# 21-M2_GNSS.net
KiCad netlist of a schematic drawn in Altium Designer
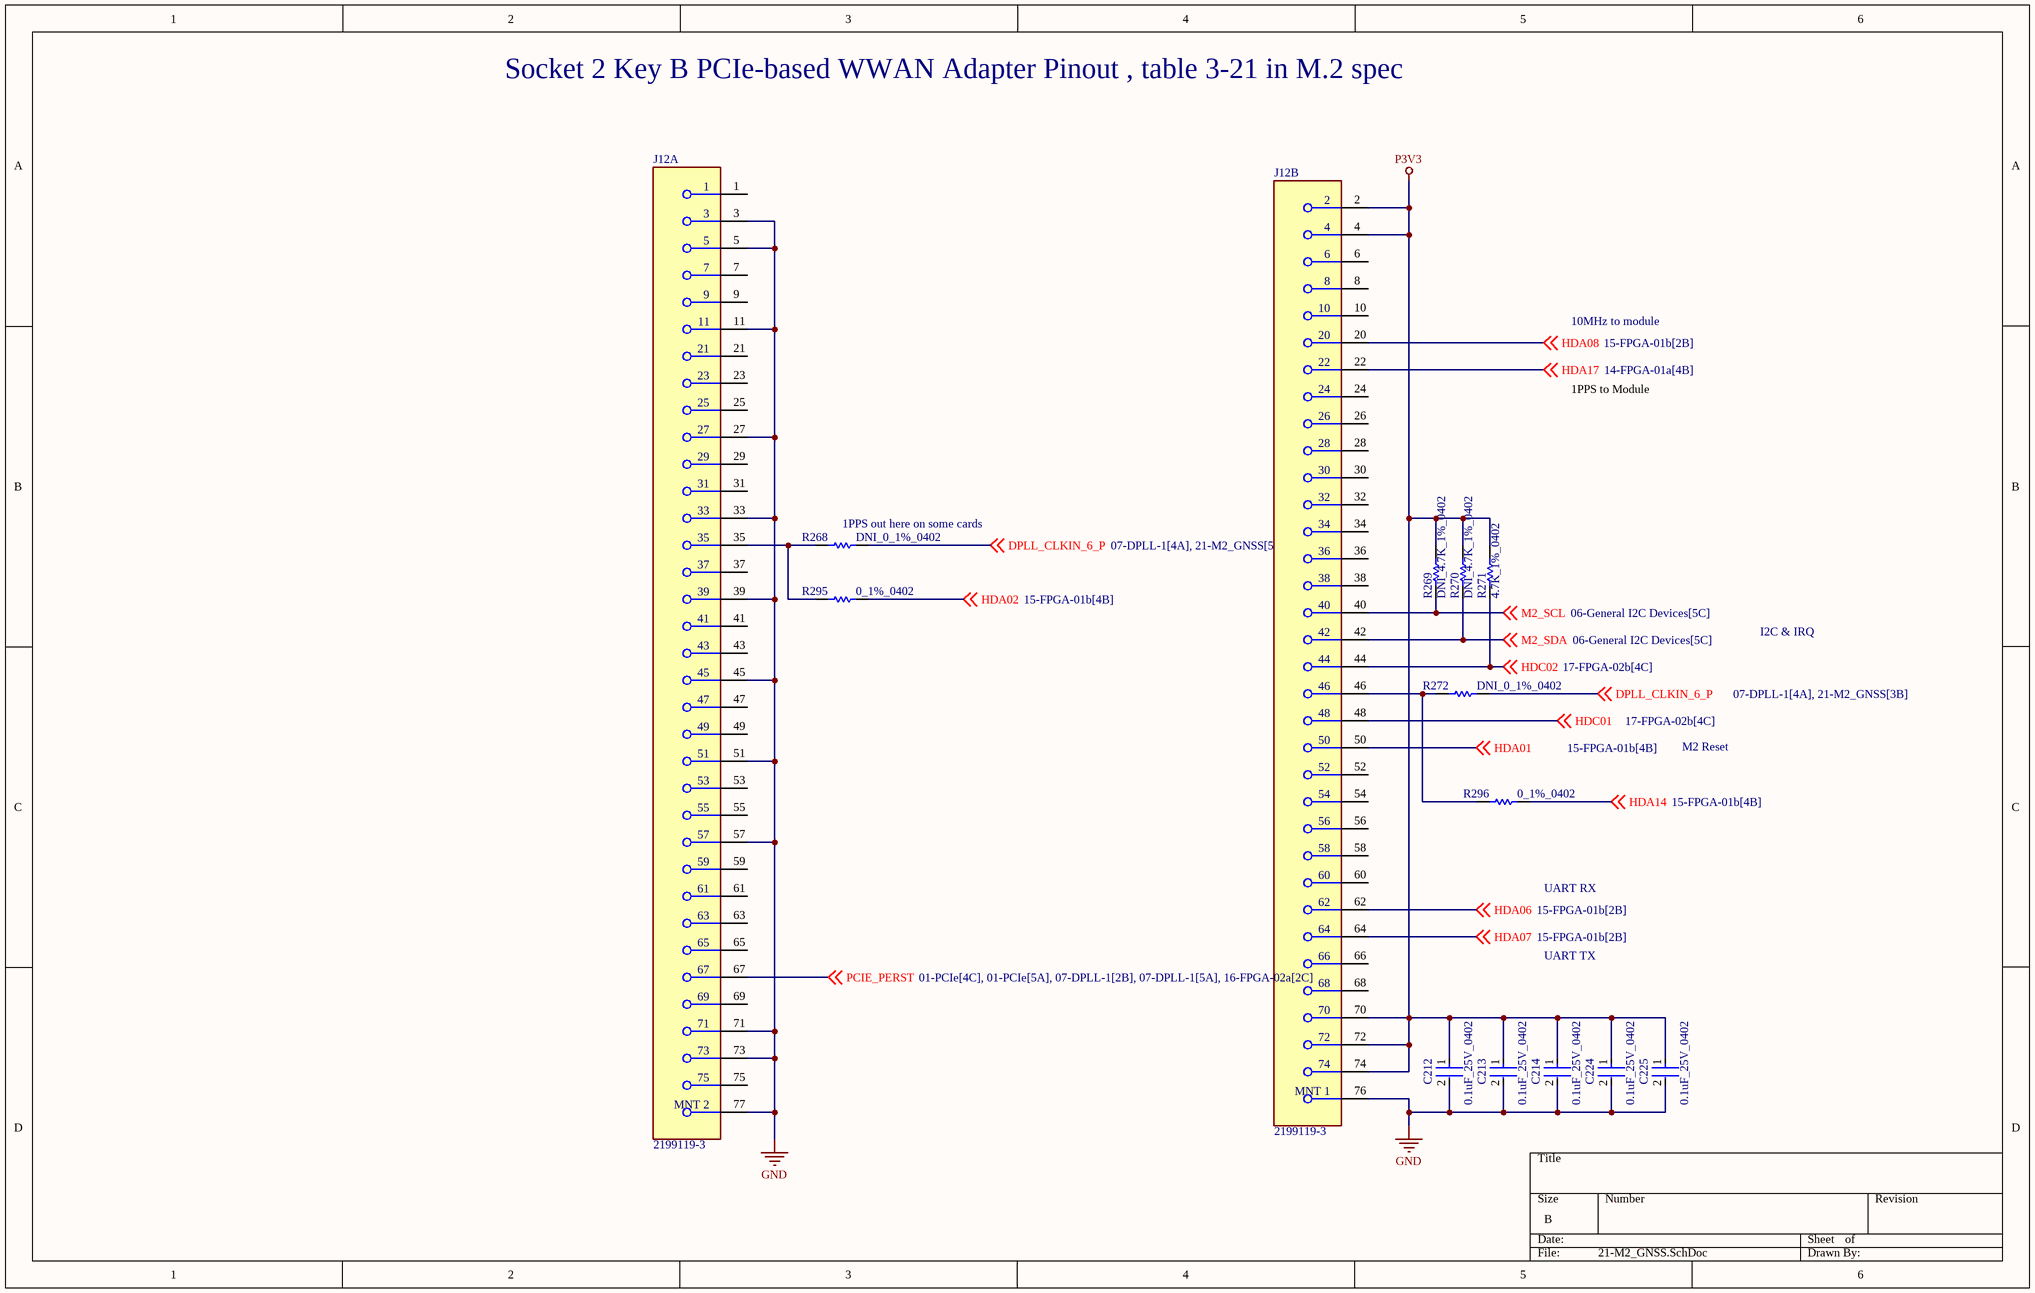
[diagram p0: 21-M2_GNSS.SchDoc]

(export (version "E")
  (design (tool "Eeschema 10.0.6"))
  (components
    (comp (ref "C212")
      (value "0.1uF_25V_0402")
      (footprint "FP-0402-L_1_0_1-W_0_5_0_1-IPC_C")
      (description "General Purpose Ceramic Capacitor, 0402, 100nF, 10%, X7R, 15%, 25V")
      (fields (field (name "VOLTAGE") "25V") (field (name "TOLERANCE") "10%"))
      (libsource (lib "Altium Content Vault") (part "b4654b650e69147ec39a6b967a45e02"))
    )
    (comp (ref "C213")
      (value "0.1uF_25V_0402")
      (footprint "FP-0402-L_1_0_1-W_0_5_0_1-IPC_C")
      (description "General Purpose Ceramic Capacitor, 0402, 100nF, 10%, X7R, 15%, 25V")
      (fields (field (name "VOLTAGE") "25V") (field (name "TOLERANCE") "10%"))
      (libsource (lib "Altium Content Vault") (part "b4654b650e69147ec39a6b967a45e02"))
    )
    (comp (ref "C214")
      (value "0.1uF_25V_0402")
      (footprint "FP-0402-L_1_0_1-W_0_5_0_1-IPC_C")
      (description "General Purpose Ceramic Capacitor, 0402, 100nF, 10%, X7R, 15%, 25V")
      (fields (field (name "VOLTAGE") "25V") (field (name "TOLERANCE") "10%"))
      (libsource (lib "Altium Content Vault") (part "b4654b650e69147ec39a6b967a45e02"))
    )
    (comp (ref "C224")
      (value "0.1uF_25V_0402")
      (footprint "FP-0402-L_1_0_1-W_0_5_0_1-IPC_C")
      (description "General Purpose Ceramic Capacitor, 0402, 100nF, 10%, X7R, 15%, 25V")
      (fields (field (name "VOLTAGE") "25V") (field (name "TOLERANCE") "10%"))
      (libsource (lib "Altium Content Vault") (part "b4654b650e69147ec39a6b967a45e02"))
    )
    (comp (ref "C225")
      (value "0.1uF_25V_0402")
      (footprint "FP-0402-L_1_0_1-W_0_5_0_1-IPC_C")
      (description "General Purpose Ceramic Capacitor, 0402, 100nF, 10%, X7R, 15%, 25V")
      (fields (field (name "VOLTAGE") "25V") (field (name "TOLERANCE") "10%"))
      (libsource (lib "Altium Content Vault") (part "b4654b650e69147ec39a6b967a45e02"))
    )
    (comp (ref "J12")
      (value "2199119-3")
      (footprint "FP-2199119-3-MFG")
      (description "CONN M.2 FEMALE 67POS 0.020 GOLD")
      (libsource (lib "Altium Content Vault") (part "a14843ccfa78e5d0b739856168502fb"))
    )
    (comp (ref "R268")
      (value "DNI_0_1%_0402")
      (footprint "RESC1005X40X25LL05T05")
      (description "Chip Resistor, 0 Ohm, 0.1 W, -55 to 155 degC, 0402 (1005 Metric), RoHS, Tape and Reel")
      (fields (field (name "MANUFACTURER") "Panasonic") (field (name "TOLERANCE") "5%"))
      (libsource (lib "Altium Content Vault") (part "RES-2"))
    )
    (comp (ref "R269")
      (value "DNI_4.7K_1%_0402")
      (footprint "RESC1005X40X25NL10T10")
      (fields (field (name "MANUFACTURER") "Bourns") (field (name "PART NUMBER") "CR0402-FX-4701GLF"))
      (libsource (lib "Altium Content Vault") (part "RES"))
    )
    (comp (ref "R270")
      (value "DNI_4.7K_1%_0402")
      (footprint "RESC1005X40X25NL10T10")
      (fields (field (name "MANUFACTURER") "Bourns") (field (name "PART NUMBER") "CR0402-FX-4701GLF"))
      (libsource (lib "Altium Content Vault") (part "RES"))
    )
    (comp (ref "R271")
      (value "4.7K_1%_0402")
      (footprint "RESC1005X40X25NL10T10")
      (fields (field (name "MANUFACTURER") "Bourns") (field (name "PART NUMBER") "CR0402-FX-4701GLF"))
      (libsource (lib "Altium Content Vault") (part "RES"))
    )
    (comp (ref "R272")
      (value "DNI_0_1%_0402")
      (footprint "RESC1005X40X25LL05T05")
      (description "Chip Resistor, 0 Ohm, 0.1 W, -55 to 155 degC, 0402 (1005 Metric), RoHS, Tape and Reel")
      (fields (field (name "MANUFACTURER") "Panasonic") (field (name "TOLERANCE") "5%"))
      (libsource (lib "Altium Content Vault") (part "RES-2"))
    )
    (comp (ref "R295")
      (value "0_1%_0402")
      (footprint "RESC1005X40X25LL05T05")
      (description "Chip Resistor, 0 Ohm, 0.1 W, -55 to 155 degC, 0402 (1005 Metric), RoHS, Tape and Reel")
      (fields (field (name "MANUFACTURER") "Panasonic") (field (name "TOLERANCE") "5%"))
      (libsource (lib "Altium Content Vault") (part "RES-2"))
    )
    (comp (ref "R296")
      (value "0_1%_0402")
      (footprint "RESC1005X40X25LL05T05")
      (description "Chip Resistor, 0 Ohm, 0.1 W, -55 to 155 degC, 0402 (1005 Metric), RoHS, Tape and Reel")
      (fields (field (name "MANUFACTURER") "Panasonic") (field (name "TOLERANCE") "5%"))
      (libsource (lib "Altium Content Vault") (part "RES-2"))
    )
  )
  (nets
    (net (code "1") (name "DPLL_CLKIN_6_P") (class "Default")
      (node (ref "R268") (pin "2") (pinfunction "2_2") (pintype "passive"))
      (node (ref "R272") (pin "2") (pinfunction "2_2") (pintype "passive"))
    )
    (net (code "2") (name "GND") (class "Default")
      (node (ref "C212") (pin "2") (pinfunction "2_2") (pintype "passive"))
      (node (ref "C213") (pin "2") (pinfunction "2_2") (pintype "passive"))
      (node (ref "C214") (pin "2") (pinfunction "2_2") (pintype "passive"))
      (node (ref "C224") (pin "2") (pinfunction "2_2") (pintype "passive"))
      (node (ref "C225") (pin "2") (pinfunction "2_2") (pintype "passive"))
      (node (ref "J12") (pin "11") (pinfunction "11_11") (pintype "passive"))
      (node (ref "J12") (pin "27") (pinfunction "27_27") (pintype "passive"))
      (node (ref "J12") (pin "3") (pinfunction "3_3") (pintype "passive"))
      (node (ref "J12") (pin "33") (pinfunction "33_33") (pintype "passive"))
      (node (ref "J12") (pin "39") (pinfunction "39_39") (pintype "passive"))
      (node (ref "J12") (pin "45") (pinfunction "45_45") (pintype "passive"))
      (node (ref "J12") (pin "5") (pinfunction "5_5") (pintype "passive"))
      (node (ref "J12") (pin "51") (pinfunction "51_51") (pintype "passive"))
      (node (ref "J12") (pin "57") (pinfunction "57_57") (pintype "passive"))
      (node (ref "J12") (pin "71") (pinfunction "71_71") (pintype "passive"))
      (node (ref "J12") (pin "73") (pinfunction "73_73") (pintype "passive"))
      (node (ref "J12") (pin "76") (pinfunction "MNT_1_76") (pintype "passive"))
      (node (ref "J12") (pin "77") (pinfunction "MNT_2_77") (pintype "passive"))
    )
    (net (code "3") (name "HDA01") (class "Default")
      (node (ref "J12") (pin "50") (pinfunction "50_50") (pintype "passive"))
    )
    (net (code "4") (name "HDA02") (class "Default")
      (node (ref "R295") (pin "2") (pinfunction "2_2") (pintype "passive"))
    )
    (net (code "5") (name "HDA06") (class "Default")
      (node (ref "J12") (pin "62") (pinfunction "62_62") (pintype "passive"))
    )
    (net (code "6") (name "HDA07") (class "Default")
      (node (ref "J12") (pin "64") (pinfunction "64_64") (pintype "passive"))
    )
    (net (code "7") (name "HDA08") (class "Default")
      (node (ref "J12") (pin "20") (pinfunction "20_20") (pintype "passive"))
    )
    (net (code "8") (name "HDA14") (class "Default")
      (node (ref "R296") (pin "2") (pinfunction "2_2") (pintype "passive"))
    )
    (net (code "9") (name "HDA17") (class "Default")
      (node (ref "J12") (pin "22") (pinfunction "22_22") (pintype "passive"))
    )
    (net (code "10") (name "HDC01") (class "Default")
      (node (ref "J12") (pin "48") (pinfunction "48_48") (pintype "passive"))
    )
    (net (code "11") (name "HDC02") (class "Default")
      (node (ref "J12") (pin "44") (pinfunction "44_44") (pintype "passive"))
      (node (ref "R271") (pin "1") (pinfunction "1_1") (pintype "passive"))
    )
    (net (code "12") (name "M2_SCL") (class "Default")
      (node (ref "J12") (pin "40") (pinfunction "40_40") (pintype "passive"))
      (node (ref "R269") (pin "1") (pinfunction "1_1") (pintype "passive"))
    )
    (net (code "13") (name "M2_SDA") (class "Default")
      (node (ref "J12") (pin "42") (pinfunction "42_42") (pintype "passive"))
      (node (ref "R270") (pin "1") (pinfunction "1_1") (pintype "passive"))
    )
    (net (code "14") (name "Net-(J12-Pad35)") (class "Default")
      (node (ref "J12") (pin "35") (pinfunction "35_35") (pintype "passive"))
      (node (ref "R268") (pin "1") (pinfunction "1_1") (pintype "passive"))
      (node (ref "R295") (pin "1") (pinfunction "1_1") (pintype "passive"))
    )
    (net (code "15") (name "Net-(J12-Pad46)") (class "Default")
      (node (ref "J12") (pin "46") (pinfunction "46_46") (pintype "passive"))
      (node (ref "R272") (pin "1") (pinfunction "1_1") (pintype "passive"))
      (node (ref "R296") (pin "1") (pinfunction "1_1") (pintype "passive"))
    )
    (net (code "16") (name "P3V3") (class "Default")
      (node (ref "C212") (pin "1") (pinfunction "1_1") (pintype "passive"))
      (node (ref "C213") (pin "1") (pinfunction "1_1") (pintype "passive"))
      (node (ref "C214") (pin "1") (pinfunction "1_1") (pintype "passive"))
      (node (ref "C224") (pin "1") (pinfunction "1_1") (pintype "passive"))
      (node (ref "C225") (pin "1") (pinfunction "1_1") (pintype "passive"))
      (node (ref "J12") (pin "2") (pinfunction "2_2") (pintype "passive"))
      (node (ref "J12") (pin "4") (pinfunction "4_4") (pintype "passive"))
      (node (ref "J12") (pin "70") (pinfunction "70_70") (pintype "passive"))
      (node (ref "J12") (pin "72") (pinfunction "72_72") (pintype "passive"))
      (node (ref "J12") (pin "74") (pinfunction "74_74") (pintype "passive"))
      (node (ref "R269") (pin "2") (pinfunction "2_2") (pintype "passive"))
      (node (ref "R270") (pin "2") (pinfunction "2_2") (pintype "passive"))
      (node (ref "R271") (pin "2") (pinfunction "2_2") (pintype "passive"))
    )
    (net (code "17") (name "PCIE_PERST") (class "Default")
      (node (ref "J12") (pin "67") (pinfunction "67_67") (pintype "passive"))
    )
    (net (code "18") (name "unconnected-(J12-Pad1)") (class "Default")
      (node (ref "J12") (pin "1") (pinfunction "1_1") (pintype "passive"))
    )
    (net (code "19") (name "unconnected-(J12-Pad6)") (class "Default")
      (node (ref "J12") (pin "6") (pinfunction "6_6") (pintype "passive"))
    )
    (net (code "20") (name "unconnected-(J12-Pad7)") (class "Default")
      (node (ref "J12") (pin "7") (pinfunction "7_7") (pintype "passive"))
    )
    (net (code "21") (name "unconnected-(J12-Pad8)") (class "Default")
      (node (ref "J12") (pin "8") (pinfunction "8_8") (pintype "passive"))
    )
    (net (code "22") (name "unconnected-(J12-Pad9)") (class "Default")
      (node (ref "J12") (pin "9") (pinfunction "9_9") (pintype "passive"))
    )
    (net (code "23") (name "unconnected-(J12-Pad10)") (class "Default")
      (node (ref "J12") (pin "10") (pinfunction "10_10") (pintype "passive"))
    )
    (net (code "24") (name "unconnected-(J12-Pad21)") (class "Default")
      (node (ref "J12") (pin "21") (pinfunction "21_21") (pintype "passive"))
    )
    (net (code "25") (name "unconnected-(J12-Pad23)") (class "Default")
      (node (ref "J12") (pin "23") (pinfunction "23_23") (pintype "passive"))
    )
    (net (code "26") (name "unconnected-(J12-Pad24)") (class "Default")
      (node (ref "J12") (pin "24") (pinfunction "24_24") (pintype "passive"))
    )
    (net (code "27") (name "unconnected-(J12-Pad25)") (class "Default")
      (node (ref "J12") (pin "25") (pinfunction "25_25") (pintype "passive"))
    )
    (net (code "28") (name "unconnected-(J12-Pad26)") (class "Default")
      (node (ref "J12") (pin "26") (pinfunction "26_26") (pintype "passive"))
    )
    (net (code "29") (name "unconnected-(J12-Pad28)") (class "Default")
      (node (ref "J12") (pin "28") (pinfunction "28_28") (pintype "passive"))
    )
    (net (code "30") (name "unconnected-(J12-Pad29)") (class "Default")
      (node (ref "J12") (pin "29") (pinfunction "29_29") (pintype "passive"))
    )
    (net (code "31") (name "unconnected-(J12-Pad30)") (class "Default")
      (node (ref "J12") (pin "30") (pinfunction "30_30") (pintype "passive"))
    )
    (net (code "32") (name "unconnected-(J12-Pad31)") (class "Default")
      (node (ref "J12") (pin "31") (pinfunction "31_31") (pintype "passive"))
    )
    (net (code "33") (name "unconnected-(J12-Pad32)") (class "Default")
      (node (ref "J12") (pin "32") (pinfunction "32_32") (pintype "passive"))
    )
    (net (code "34") (name "unconnected-(J12-Pad34)") (class "Default")
      (node (ref "J12") (pin "34") (pinfunction "34_34") (pintype "passive"))
    )
    (net (code "35") (name "unconnected-(J12-Pad36)") (class "Default")
      (node (ref "J12") (pin "36") (pinfunction "36_36") (pintype "passive"))
    )
    (net (code "36") (name "unconnected-(J12-Pad37)") (class "Default")
      (node (ref "J12") (pin "37") (pinfunction "37_37") (pintype "passive"))
    )
    (net (code "37") (name "unconnected-(J12-Pad38)") (class "Default")
      (node (ref "J12") (pin "38") (pinfunction "38_38") (pintype "passive"))
    )
    (net (code "38") (name "unconnected-(J12-Pad41)") (class "Default")
      (node (ref "J12") (pin "41") (pinfunction "41_41") (pintype "passive"))
    )
    (net (code "39") (name "unconnected-(J12-Pad43)") (class "Default")
      (node (ref "J12") (pin "43") (pinfunction "43_43") (pintype "passive"))
    )
    (net (code "40") (name "unconnected-(J12-Pad47)") (class "Default")
      (node (ref "J12") (pin "47") (pinfunction "47_47") (pintype "passive"))
    )
    (net (code "41") (name "unconnected-(J12-Pad49)") (class "Default")
      (node (ref "J12") (pin "49") (pinfunction "49_49") (pintype "passive"))
    )
    (net (code "42") (name "unconnected-(J12-Pad52)") (class "Default")
      (node (ref "J12") (pin "52") (pinfunction "52_52") (pintype "passive"))
    )
    (net (code "43") (name "unconnected-(J12-Pad53)") (class "Default")
      (node (ref "J12") (pin "53") (pinfunction "53_53") (pintype "passive"))
    )
    (net (code "44") (name "unconnected-(J12-Pad54)") (class "Default")
      (node (ref "J12") (pin "54") (pinfunction "54_54") (pintype "passive"))
    )
    (net (code "45") (name "unconnected-(J12-Pad55)") (class "Default")
      (node (ref "J12") (pin "55") (pinfunction "55_55") (pintype "passive"))
    )
    (net (code "46") (name "unconnected-(J12-Pad56)") (class "Default")
      (node (ref "J12") (pin "56") (pinfunction "56_56") (pintype "passive"))
    )
    (net (code "47") (name "unconnected-(J12-Pad58)") (class "Default")
      (node (ref "J12") (pin "58") (pinfunction "58_58") (pintype "passive"))
    )
    (net (code "48") (name "unconnected-(J12-Pad59)") (class "Default")
      (node (ref "J12") (pin "59") (pinfunction "59_59") (pintype "passive"))
    )
    (net (code "49") (name "unconnected-(J12-Pad60)") (class "Default")
      (node (ref "J12") (pin "60") (pinfunction "60_60") (pintype "passive"))
    )
    (net (code "50") (name "unconnected-(J12-Pad61)") (class "Default")
      (node (ref "J12") (pin "61") (pinfunction "61_61") (pintype "passive"))
    )
    (net (code "51") (name "unconnected-(J12-Pad63)") (class "Default")
      (node (ref "J12") (pin "63") (pinfunction "63_63") (pintype "passive"))
    )
    (net (code "52") (name "unconnected-(J12-Pad65)") (class "Default")
      (node (ref "J12") (pin "65") (pinfunction "65_65") (pintype "passive"))
    )
    (net (code "53") (name "unconnected-(J12-Pad66)") (class "Default")
      (node (ref "J12") (pin "66") (pinfunction "66_66") (pintype "passive"))
    )
    (net (code "54") (name "unconnected-(J12-Pad68)") (class "Default")
      (node (ref "J12") (pin "68") (pinfunction "68_68") (pintype "passive"))
    )
    (net (code "55") (name "unconnected-(J12-Pad69)") (class "Default")
      (node (ref "J12") (pin "69") (pinfunction "69_69") (pintype "passive"))
    )
    (net (code "56") (name "unconnected-(J12-Pad75)") (class "Default")
      (node (ref "J12") (pin "75") (pinfunction "75_75") (pintype "passive"))
    )
  )
)
